# Power.net
KiCad netlist of a schematic drawn in Altium Designer
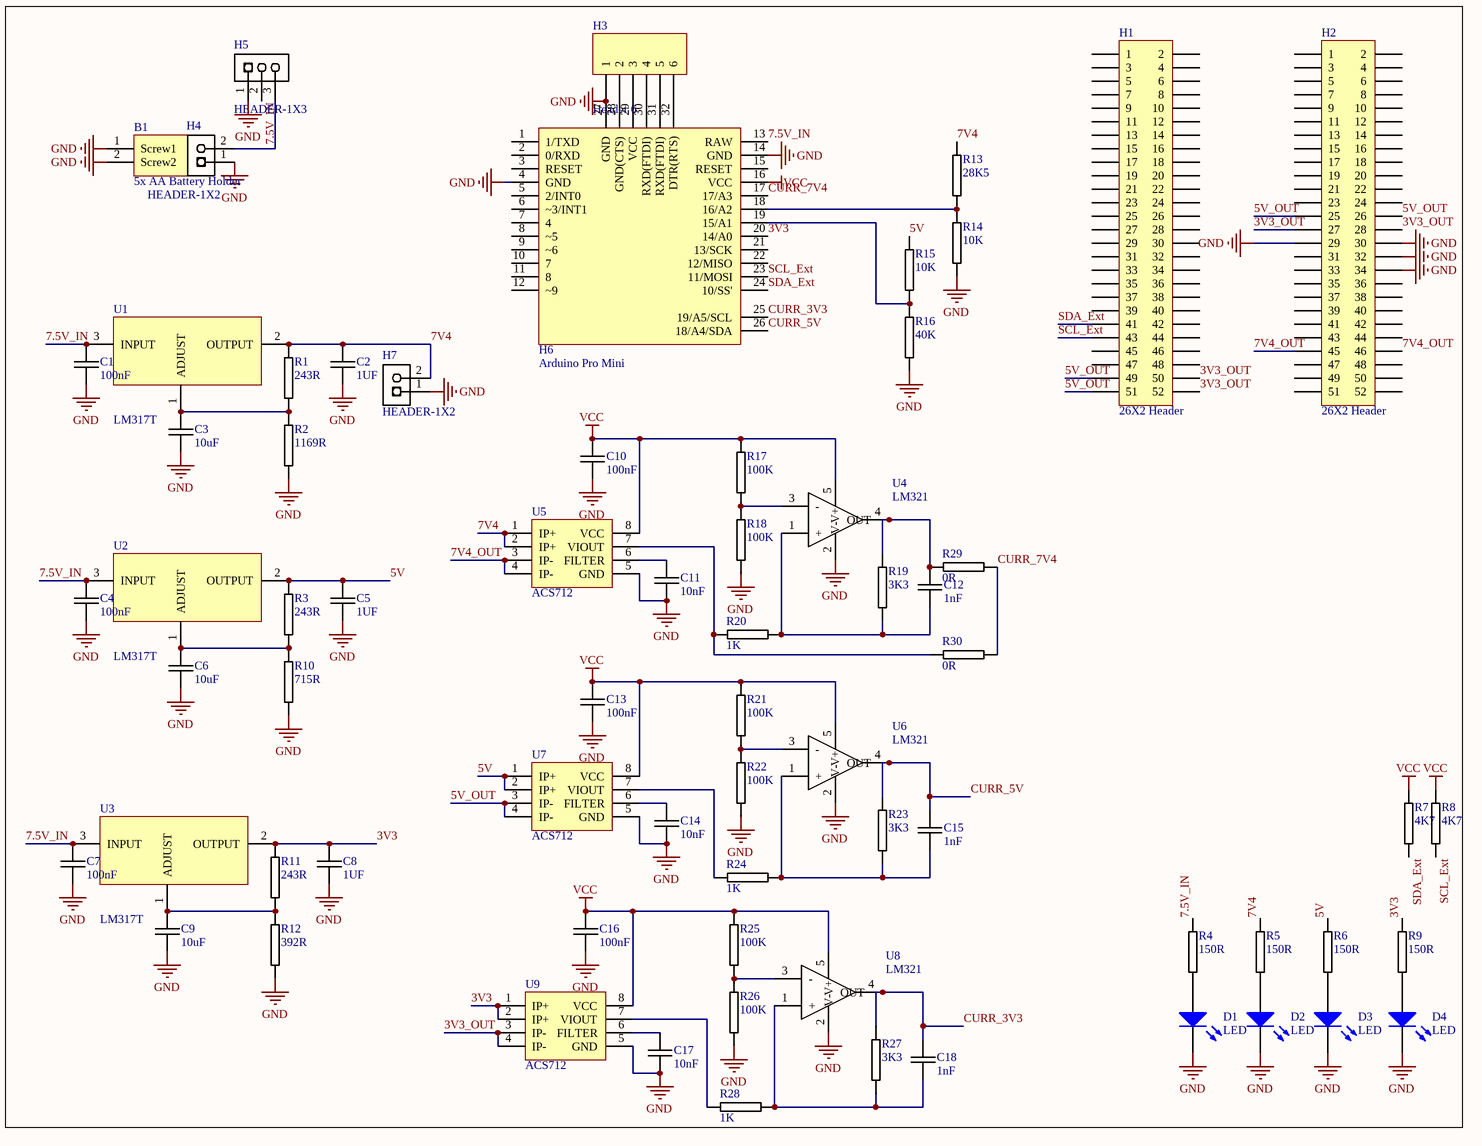
[diagram p0: Power.SchDoc]

(export (version "E")
  (design (tool "Eeschema 10.0.6"))
  (components
    (comp (ref "B1")
      (value "5x AA Battery Holder")
      (footprint "5x AA Battery Holder")
      (libsource (lib "Components") (part "5x AA Battery Holder"))
    )
    (comp (ref "C1")
      (value "100nF")
      (footprint "0805C-TBD")
      (description "CAPACITOR 0805 CERAMIC")
      (libsource (lib "vh_altium_library") (part "0805C-100nF-25V-X7R-MUR"))
    )
    (comp (ref "C2")
      (value "1UF")
      (footprint "0805C-GENERIC")
      (description "CAPACITOR 0805 CERAMIC")
      (fields
        (field (name "MANUFACTURER PART NUMBER") "ECJ-1VB0J225K")
        (field (name "MANUFACTURER") "Panasonic - ECG")
      )
      (libsource (lib "vh_altium_library") (part "0805C-2U2-6V3-X5R-PAN"))
    )
    (comp (ref "C3")
      (value "10uF")
      (footprint "0805C-GENERIC")
      (description "CAPACITOR 0805 CERAMIC")
      (libsource (lib "vh_altium_library") (part "0805C-10UF-25V-X5R-SAM"))
    )
    (comp (ref "C4")
      (value "100nF")
      (footprint "0805C-TBD")
      (description "CAPACITOR 0805 CERAMIC")
      (libsource (lib "vh_altium_library") (part "0805C-100nF-25V-X7R-MUR"))
    )
    (comp (ref "C5")
      (value "1UF")
      (footprint "0805C-GENERIC")
      (description "CAPACITOR 0805 CERAMIC")
      (fields
        (field (name "MANUFACTURER PART NUMBER") "ECJ-1VB0J225K")
        (field (name "MANUFACTURER") "Panasonic - ECG")
      )
      (libsource (lib "vh_altium_library") (part "0805C-2U2-6V3-X5R-PAN"))
    )
    (comp (ref "C6")
      (value "10uF")
      (footprint "0805C-GENERIC")
      (description "CAPACITOR 0805 CERAMIC")
      (libsource (lib "vh_altium_library") (part "0805C-10UF-25V-X5R-SAM"))
    )
    (comp (ref "C7")
      (value "100nF")
      (footprint "0805C-TBD")
      (description "CAPACITOR 0805 CERAMIC")
      (libsource (lib "vh_altium_library") (part "0805C-100nF-25V-X7R-MUR"))
    )
    (comp (ref "C8")
      (value "1UF")
      (footprint "0805C-GENERIC")
      (description "CAPACITOR 0805 CERAMIC")
      (fields
        (field (name "MANUFACTURER PART NUMBER") "ECJ-1VB0J225K")
        (field (name "MANUFACTURER") "Panasonic - ECG")
      )
      (libsource (lib "vh_altium_library") (part "0805C-2U2-6V3-X5R-PAN"))
    )
    (comp (ref "C9")
      (value "10uF")
      (footprint "0805C-GENERIC")
      (description "CAPACITOR 0805 CERAMIC")
      (libsource (lib "vh_altium_library") (part "0805C-10UF-25V-X5R-SAM"))
    )
    (comp (ref "C10")
      (value "100nF")
      (footprint "0805C-TBD")
      (description "CAPACITOR 0805 CERAMIC")
      (libsource (lib "vh_altium_library") (part "0805C-100nF-25V-X7R-MUR"))
    )
    (comp (ref "C11")
      (value "10nF")
      (footprint "0805C-TBD")
      (description "CAPACITOR 0805 CERAMIC")
      (libsource (lib "vh_altium_library") (part "0805C-100nF-25V-X7R-MUR"))
    )
    (comp (ref "C12")
      (value "1nF")
      (footprint "0805C-TBD")
      (description "CAPACITOR 0805 CERAMIC")
      (libsource (lib "vh_altium_library") (part "0805C-100nF-25V-X7R-MUR"))
    )
    (comp (ref "C13")
      (value "100nF")
      (footprint "0805C-TBD")
      (description "CAPACITOR 0805 CERAMIC")
      (libsource (lib "vh_altium_library") (part "0805C-100nF-25V-X7R-MUR"))
    )
    (comp (ref "C14")
      (value "10nF")
      (footprint "0805C-TBD")
      (description "CAPACITOR 0805 CERAMIC")
      (libsource (lib "vh_altium_library") (part "0805C-100nF-25V-X7R-MUR"))
    )
    (comp (ref "C15")
      (value "1nF")
      (footprint "0805C-TBD")
      (description "CAPACITOR 0805 CERAMIC")
      (libsource (lib "vh_altium_library") (part "0805C-100nF-25V-X7R-MUR"))
    )
    (comp (ref "C16")
      (value "100nF")
      (footprint "0805C-TBD")
      (description "CAPACITOR 0805 CERAMIC")
      (libsource (lib "vh_altium_library") (part "0805C-100nF-25V-X7R-MUR"))
    )
    (comp (ref "C17")
      (value "10nF")
      (footprint "0805C-TBD")
      (description "CAPACITOR 0805 CERAMIC")
      (libsource (lib "vh_altium_library") (part "0805C-100nF-25V-X7R-MUR"))
    )
    (comp (ref "C18")
      (value "1nF")
      (footprint "0805C-TBD")
      (description "CAPACITOR 0805 CERAMIC")
      (libsource (lib "vh_altium_library") (part "0805C-100nF-25V-X7R-MUR"))
    )
    (comp (ref "D1")
      (value "LED")
      (footprint "LED")
      (description "Small LED")
      (libsource (lib "Components") (part "LED"))
    )
    (comp (ref "D2")
      (value "LED")
      (footprint "LED")
      (description "Small LED")
      (libsource (lib "Components") (part "LED"))
    )
    (comp (ref "D3")
      (value "LED")
      (footprint "LED")
      (description "Small LED")
      (libsource (lib "Components") (part "LED"))
    )
    (comp (ref "D4")
      (value "LED")
      (footprint "LED")
      (description "Small LED")
      (libsource (lib "Components") (part "LED"))
    )
    (comp (ref "H1")
      (value "26X2 Header")
      (footprint "26X2 Header")
      (libsource (lib "CustomParts") (part "26X2 Header"))
    )
    (comp (ref "H2")
      (value "26X2 Header")
      (footprint "26X2 Header")
      (libsource (lib "CustomParts") (part "26X2 Header"))
    )
    (comp (ref "H3")
      (value "Header 6")
      (footprint "HDR1X6")
      (description "Header, 6-Pin")
      (fields (field (name "PUBLISHER") "Altium Limited"))
      (libsource (lib "Miscellaneous Connectors") (part "Header 6"))
    )
    (comp (ref "H4")
      (value "HEADER-1X2")
      (footprint "HEADER-1X2")
      (libsource (lib "vh_altium_library") (part "HEADER-1X2"))
    )
    (comp (ref "H5")
      (value "HEADER-1X3")
      (footprint "HEADER-1X3")
      (libsource (lib "vh_altium_library") (part "HEADER-1X3"))
    )
    (comp (ref "H6")
      (value "Arduino Pro Mini")
      (footprint "Arduino Pro Mini")
      (libsource (lib "Components") (part "Arduino Pro Mini"))
    )
    (comp (ref "H7")
      (value "HEADER-1X2")
      (footprint "HEADER-1X2")
      (libsource (lib "vh_altium_library") (part "HEADER-1X2"))
    )
    (comp (ref "R1")
      (value "243R")
      (footprint "0805R-GENERIC")
      (description "RESISTOR 0805 1/3 WATT")
      (libsource (lib "vh_altium_library") (part "0805R-1R"))
    )
    (comp (ref "R2")
      (value "1169R")
      (footprint "0805R-GENERIC")
      (description "RESISTOR 0805 1/3 WATT")
      (libsource (lib "vh_altium_library") (part "0805R-1R"))
    )
    (comp (ref "R3")
      (value "243R")
      (footprint "0805R-GENERIC")
      (description "RESISTOR 0805 1/3 WATT")
      (libsource (lib "vh_altium_library") (part "0805R-1R"))
    )
    (comp (ref "R4")
      (value "150R")
      (footprint "0805R-150")
      (description "RESISTOR 0805 1/4 WATT THIN FILM")
      (libsource (lib "vh_altium_library") (part "0805R-150"))
    )
    (comp (ref "R5")
      (value "150R")
      (footprint "0805R-150")
      (description "RESISTOR 0805 1/4 WATT THIN FILM")
      (libsource (lib "vh_altium_library") (part "0805R-150"))
    )
    (comp (ref "R6")
      (value "150R")
      (footprint "0805R-150")
      (description "RESISTOR 0805 1/4 WATT THIN FILM")
      (libsource (lib "vh_altium_library") (part "0805R-150"))
    )
    (comp (ref "R7")
      (value "4K7")
      (footprint "0805R-4K7")
      (description "RESISTOR 0805 1/4 WATT THIN FILM")
      (libsource (lib "vh_altium_library") (part "0805R-4K7"))
    )
    (comp (ref "R8")
      (value "4K7")
      (footprint "0805R-4K7")
      (description "RESISTOR 0805 1/4 WATT THIN FILM")
      (libsource (lib "vh_altium_library") (part "0805R-4K7"))
    )
    (comp (ref "R9")
      (value "150R")
      (footprint "0805R-150")
      (description "RESISTOR 0805 1/4 WATT THIN FILM")
      (libsource (lib "vh_altium_library") (part "0805R-150"))
    )
    (comp (ref "R10")
      (value "715R")
      (footprint "0805R-GENERIC")
      (description "RESISTOR 0805 1/3 WATT")
      (libsource (lib "vh_altium_library") (part "0805R-1R"))
    )
    (comp (ref "R11")
      (value "243R")
      (footprint "0805R-GENERIC")
      (description "RESISTOR 0805 1/3 WATT")
      (libsource (lib "vh_altium_library") (part "0805R-1R"))
    )
    (comp (ref "R12")
      (value "392R")
      (footprint "0805R-GENERIC")
      (description "RESISTOR 0805 1/3 WATT")
      (libsource (lib "vh_altium_library") (part "0805R-1R"))
    )
    (comp (ref "R13")
      (value "28K5")
      (footprint "0805R-10K")
      (description "RESISTOR 0805 1/4 WATT THIN FILM")
      (libsource (lib "vh_altium_library") (part "0805R-10K"))
    )
    (comp (ref "R14")
      (value "10K")
      (footprint "0805R-10K")
      (description "RESISTOR 0805 1/4 WATT THIN FILM")
      (libsource (lib "vh_altium_library") (part "0805R-10K"))
    )
    (comp (ref "R15")
      (value "10K")
      (footprint "0805R-10K")
      (description "RESISTOR 0805 1/4 WATT THIN FILM")
      (libsource (lib "vh_altium_library") (part "0805R-10K"))
    )
    (comp (ref "R16")
      (value "40K")
      (footprint "0805R-10K")
      (description "RESISTOR 0805 1/4 WATT THIN FILM")
      (libsource (lib "vh_altium_library") (part "0805R-10K"))
    )
    (comp (ref "R17")
      (value "100K")
      (footprint "0805R-100K")
      (description "RESISTOR 0805 1/4 WATT THIN FILM")
      (libsource (lib "vh_altium_library") (part "0805R-100K"))
    )
    (comp (ref "R18")
      (value "100K")
      (footprint "0805R-100K")
      (description "RESISTOR 0805 1/4 WATT THIN FILM")
      (libsource (lib "vh_altium_library") (part "0805R-100K"))
    )
    (comp (ref "R19")
      (value "3K3")
      (footprint "0805R-3K3")
      (description "RESISTOR 0805 1/4 WATT THIN FILM")
      (libsource (lib "vh_altium_library") (part "0805R-3K3"))
    )
    (comp (ref "R20")
      (value "1K")
      (footprint "0805R-1K")
      (description "RESISTOR 0805 1/4 WATT THIN FILM")
      (libsource (lib "vh_altium_library") (part "0805R-1K"))
    )
    (comp (ref "R21")
      (value "100K")
      (footprint "0805R-100K")
      (description "RESISTOR 0805 1/4 WATT THIN FILM")
      (libsource (lib "vh_altium_library") (part "0805R-100K"))
    )
    (comp (ref "R22")
      (value "100K")
      (footprint "0805R-100K")
      (description "RESISTOR 0805 1/4 WATT THIN FILM")
      (libsource (lib "vh_altium_library") (part "0805R-100K"))
    )
    (comp (ref "R23")
      (value "3K3")
      (footprint "0805R-3K3")
      (description "RESISTOR 0805 1/4 WATT THIN FILM")
      (libsource (lib "vh_altium_library") (part "0805R-3K3"))
    )
    (comp (ref "R24")
      (value "1K")
      (footprint "0805R-1K")
      (description "RESISTOR 0805 1/4 WATT THIN FILM")
      (libsource (lib "vh_altium_library") (part "0805R-1K"))
    )
    (comp (ref "R25")
      (value "100K")
      (footprint "0805R-100K")
      (description "RESISTOR 0805 1/4 WATT THIN FILM")
      (libsource (lib "vh_altium_library") (part "0805R-100K"))
    )
    (comp (ref "R26")
      (value "100K")
      (footprint "0805R-100K")
      (description "RESISTOR 0805 1/4 WATT THIN FILM")
      (libsource (lib "vh_altium_library") (part "0805R-100K"))
    )
    (comp (ref "R27")
      (value "3K3")
      (footprint "0805R-3K3")
      (description "RESISTOR 0805 1/4 WATT THIN FILM")
      (libsource (lib "vh_altium_library") (part "0805R-3K3"))
    )
    (comp (ref "R28")
      (value "1K")
      (footprint "0805R-1K")
      (description "RESISTOR 0805 1/4 WATT THIN FILM")
      (libsource (lib "vh_altium_library") (part "0805R-1K"))
    )
    (comp (ref "R29")
      (value "0R")
      (footprint "0805R-GENERIC")
      (description "RESISTOR 0805 1 WATT")
      (libsource (lib "vh_altium_library") (part "0805R-0R"))
    )
    (comp (ref "R30")
      (value "0R")
      (footprint "0805R-GENERIC")
      (description "RESISTOR 0805 1 WATT")
      (libsource (lib "vh_altium_library") (part "0805R-0R"))
    )
    (comp (ref "U1")
      (value "LM317T")
      (footprint "LM317T")
      (description "Adjustable Voltage Regulator")
      (libsource (lib "Components") (part "LM317T"))
    )
    (comp (ref "U2")
      (value "LM317T")
      (footprint "LM317T")
      (description "Adjustable Voltage Regulator")
      (libsource (lib "Components") (part "LM317T"))
    )
    (comp (ref "U3")
      (value "LM317T")
      (footprint "LM317T")
      (description "Adjustable Voltage Regulator")
      (libsource (lib "Components") (part "LM317T"))
    )
    (comp (ref "U4")
      (value "LM321")
      (footprint "LM321")
      (description "Op-amp")
      (libsource (lib "Components") (part "LM321"))
    )
    (comp (ref "U5")
      (value "ACS712")
      (footprint "ACS712")
      (description "Current Sensor")
      (libsource (lib "Components") (part "ACS712"))
    )
    (comp (ref "U6")
      (value "LM321")
      (footprint "LM321")
      (description "Op-amp")
      (libsource (lib "Components") (part "LM321"))
    )
    (comp (ref "U7")
      (value "ACS712")
      (footprint "ACS712")
      (description "Current Sensor")
      (libsource (lib "Components") (part "ACS712"))
    )
    (comp (ref "U8")
      (value "LM321")
      (footprint "LM321")
      (description "Op-amp")
      (libsource (lib "Components") (part "LM321"))
    )
    (comp (ref "U9")
      (value "ACS712")
      (footprint "ACS712")
      (description "Current Sensor")
      (libsource (lib "Components") (part "ACS712"))
    )
  )
  (nets
    (net (code "1") (name "/3V3") (class "Default")
      (node (ref "C8") (pin "1") (pintype "passive"))
      (node (ref "H6") (pin "20") (pinfunction "14/A0_20") (pintype "passive"))
      (node (ref "R11") (pin "2") (pintype "passive"))
      (node (ref "R9") (pin "1") (pintype "passive"))
      (node (ref "U3") (pin "2") (pinfunction "OUTPUT_2") (pintype "passive"))
      (node (ref "U9") (pin "1") (pinfunction "IP+_1") (pintype "passive"))
      (node (ref "U9") (pin "2") (pinfunction "IP+_2") (pintype "passive"))
    )
    (net (code "2") (name "/3V3_OUT") (class "Default")
      (node (ref "H1") (pin "50") (pinfunction "50_50") (pintype "passive"))
      (node (ref "H1") (pin "52") (pinfunction "52_52") (pintype "passive"))
      (node (ref "H2") (pin "27") (pinfunction "27_27") (pintype "passive"))
      (node (ref "H2") (pin "28") (pinfunction "28_28") (pintype "passive"))
      (node (ref "U9") (pin "3") (pinfunction "IP-_3") (pintype "passive"))
      (node (ref "U9") (pin "4") (pinfunction "IP-_4") (pintype "passive"))
    )
    (net (code "3") (name "/5V") (class "Default")
      (node (ref "C5") (pin "1") (pintype "passive"))
      (node (ref "R15") (pin "1") (pintype "passive"))
      (node (ref "R3") (pin "2") (pintype "passive"))
      (node (ref "R6") (pin "1") (pintype "passive"))
      (node (ref "U2") (pin "2") (pinfunction "OUTPUT_2") (pintype "passive"))
      (node (ref "U7") (pin "1") (pinfunction "IP+_1") (pintype "passive"))
      (node (ref "U7") (pin "2") (pinfunction "IP+_2") (pintype "passive"))
    )
    (net (code "4") (name "/5V_OUT") (class "Default")
      (node (ref "H1") (pin "49") (pinfunction "49_49") (pintype "passive"))
      (node (ref "H1") (pin "51") (pinfunction "51_51") (pintype "passive"))
      (node (ref "H2") (pin "25") (pinfunction "25_25") (pintype "passive"))
      (node (ref "H2") (pin "26") (pinfunction "26_26") (pintype "passive"))
      (node (ref "U7") (pin "3") (pinfunction "IP-_3") (pintype "passive"))
      (node (ref "U7") (pin "4") (pinfunction "IP-_4") (pintype "passive"))
    )
    (net (code "5") (name "/7.5V_IN") (class "Default")
      (node (ref "C1") (pin "1") (pintype "passive"))
      (node (ref "C4") (pin "1") (pintype "passive"))
      (node (ref "C7") (pin "1") (pintype "passive"))
      (node (ref "H5") (pin "2") (pintype "passive"))
      (node (ref "H6") (pin "13") (pinfunction "RAW_13") (pintype "passive"))
      (node (ref "R4") (pin "1") (pintype "passive"))
      (node (ref "U1") (pin "3") (pinfunction "INPUT_3") (pintype "passive"))
      (node (ref "U2") (pin "3") (pinfunction "INPUT_3") (pintype "passive"))
      (node (ref "U3") (pin "3") (pinfunction "INPUT_3") (pintype "passive"))
    )
    (net (code "6") (name "/7V4") (class "Default")
      (node (ref "C2") (pin "1") (pintype "passive"))
      (node (ref "H7") (pin "2") (pintype "passive"))
      (node (ref "R1") (pin "2") (pintype "passive"))
      (node (ref "R13") (pin "1") (pintype "passive"))
      (node (ref "R5") (pin "1") (pintype "passive"))
      (node (ref "U1") (pin "2") (pinfunction "OUTPUT_2") (pintype "passive"))
      (node (ref "U5") (pin "1") (pinfunction "IP+_1") (pintype "passive"))
      (node (ref "U5") (pin "2") (pinfunction "IP+_2") (pintype "passive"))
    )
    (net (code "7") (name "/7V4_OUT") (class "Default")
      (node (ref "H2") (pin "45") (pinfunction "45_45") (pintype "passive"))
      (node (ref "H2") (pin "46") (pinfunction "46_46") (pintype "passive"))
      (node (ref "U5") (pin "3") (pinfunction "IP-_3") (pintype "passive"))
      (node (ref "U5") (pin "4") (pinfunction "IP-_4") (pintype "passive"))
    )
    (net (code "8") (name "/CURR_3V3") (class "Default")
      (node (ref "C18") (pin "1") (pintype "passive"))
      (node (ref "H6") (pin "25") (pinfunction "19/A5/SCL_25") (pintype "passive"))
      (node (ref "R27") (pin "1") (pintype "passive"))
      (node (ref "U8") (pin "4") (pinfunction "OUT_4") (pintype "passive"))
    )
    (net (code "9") (name "/CURR_5V") (class "Default")
      (node (ref "C15") (pin "1") (pintype "passive"))
      (node (ref "H6") (pin "26") (pinfunction "18/A4/SDA_26") (pintype "passive"))
      (node (ref "R23") (pin "1") (pintype "passive"))
      (node (ref "U6") (pin "4") (pinfunction "OUT_4") (pintype "passive"))
    )
    (net (code "10") (name "/CURR_7V4") (class "Default")
      (node (ref "H6") (pin "17") (pinfunction "17/A3_17") (pintype "passive"))
      (node (ref "R29") (pin "2") (pintype "passive"))
      (node (ref "R30") (pin "2") (pintype "passive"))
    )
    (net (code "11") (name "/SCL_Ext") (class "Default")
      (node (ref "H1") (pin "43") (pinfunction "43_43") (pintype "passive"))
      (node (ref "H6") (pin "23") (pinfunction "11/MOSI_23") (pintype "passive"))
      (node (ref "R8") (pin "2") (pintype "passive"))
    )
    (net (code "12") (name "/SDA_Ext") (class "Default")
      (node (ref "H1") (pin "41") (pinfunction "41_41") (pintype "passive"))
      (node (ref "H6") (pin "24") (pinfunction "10/SS'_24") (pintype "passive"))
      (node (ref "R7") (pin "2") (pintype "passive"))
    )
    (net (code "13") (name "GND") (class "Default")
      (node (ref "B1") (pin "1") (pinfunction "Screw1_1") (pintype "passive"))
      (node (ref "B1") (pin "2") (pinfunction "Screw2_2") (pintype "passive"))
      (node (ref "C1") (pin "2") (pintype "passive"))
      (node (ref "C10") (pin "2") (pintype "passive"))
      (node (ref "C11") (pin "2") (pintype "passive"))
      (node (ref "C13") (pin "2") (pintype "passive"))
      (node (ref "C14") (pin "2") (pintype "passive"))
      (node (ref "C16") (pin "2") (pintype "passive"))
      (node (ref "C17") (pin "2") (pintype "passive"))
      (node (ref "C2") (pin "2") (pintype "passive"))
      (node (ref "C3") (pin "2") (pintype "passive"))
      (node (ref "C4") (pin "2") (pintype "passive"))
      (node (ref "C5") (pin "2") (pintype "passive"))
      (node (ref "C6") (pin "2") (pintype "passive"))
      (node (ref "C7") (pin "2") (pintype "passive"))
      (node (ref "C8") (pin "2") (pintype "passive"))
      (node (ref "C9") (pin "2") (pintype "passive"))
      (node (ref "D1") (pin "2") (pinfunction "K_2") (pintype "passive"))
      (node (ref "D2") (pin "2") (pinfunction "K_2") (pintype "passive"))
      (node (ref "D3") (pin "2") (pinfunction "K_2") (pintype "passive"))
      (node (ref "D4") (pin "2") (pinfunction "K_2") (pintype "passive"))
      (node (ref "H2") (pin "29") (pinfunction "29_29") (pintype "passive"))
      (node (ref "H2") (pin "30") (pinfunction "30_30") (pintype "passive"))
      (node (ref "H2") (pin "32") (pinfunction "32_32") (pintype "passive"))
      (node (ref "H2") (pin "34") (pinfunction "34_34") (pintype "passive"))
      (node (ref "H3") (pin "1") (pinfunction "1_1") (pintype "passive"))
      (node (ref "H4") (pin "1") (pintype "passive"))
      (node (ref "H5") (pin "1") (pintype "passive"))
      (node (ref "H6") (pin "14") (pinfunction "GND_14") (pintype "passive"))
      (node (ref "H6") (pin "27") (pinfunction "GND_27") (pintype "passive"))
      (node (ref "H6") (pin "4") (pinfunction "GND_4") (pintype "passive"))
      (node (ref "H7") (pin "1") (pintype "passive"))
      (node (ref "R10") (pin "2") (pintype "passive"))
      (node (ref "R12") (pin "2") (pintype "passive"))
      (node (ref "R14") (pin "2") (pintype "passive"))
      (node (ref "R16") (pin "2") (pintype "passive"))
      (node (ref "R18") (pin "2") (pintype "passive"))
      (node (ref "R2") (pin "2") (pintype "passive"))
      (node (ref "R22") (pin "2") (pintype "passive"))
      (node (ref "R26") (pin "2") (pintype "passive"))
      (node (ref "U4") (pin "2") (pinfunction "V-_2") (pintype "passive"))
      (node (ref "U5") (pin "5") (pinfunction "GND_5") (pintype "passive"))
      (node (ref "U6") (pin "2") (pinfunction "V-_2") (pintype "passive"))
      (node (ref "U7") (pin "5") (pinfunction "GND_5") (pintype "passive"))
      (node (ref "U8") (pin "2") (pinfunction "V-_2") (pintype "passive"))
      (node (ref "U9") (pin "5") (pinfunction "GND_5") (pintype "passive"))
    )
    (net (code "14") (name "Net-(D1-A)") (class "Default")
      (node (ref "D1") (pin "1") (pinfunction "A_1") (pintype "passive"))
      (node (ref "R4") (pin "2") (pintype "passive"))
    )
    (net (code "15") (name "Net-(D2-A)") (class "Default")
      (node (ref "D2") (pin "1") (pinfunction "A_1") (pintype "passive"))
      (node (ref "R5") (pin "2") (pintype "passive"))
    )
    (net (code "16") (name "Net-(D3-A)") (class "Default")
      (node (ref "D3") (pin "1") (pinfunction "A_1") (pintype "passive"))
      (node (ref "R6") (pin "2") (pintype "passive"))
    )
    (net (code "17") (name "Net-(D4-A)") (class "Default")
      (node (ref "D4") (pin "1") (pinfunction "A_1") (pintype "passive"))
      (node (ref "R9") (pin "2") (pintype "passive"))
    )
    (net (code "18") (name "Net-(H3-Pad3)") (class "Default")
      (node (ref "H3") (pin "3") (pinfunction "3_3") (pintype "passive"))
      (node (ref "H6") (pin "29") (pinfunction "VCC_29") (pintype "passive"))
    )
    (net (code "19") (name "Net-(H3-Pad4)") (class "Default")
      (node (ref "H3") (pin "4") (pinfunction "4_4") (pintype "passive"))
      (node (ref "H6") (pin "30") (pinfunction "RXD(FTDI)_30") (pintype "passive"))
    )
    (net (code "20") (name "Net-(H3-Pad5)") (class "Default")
      (node (ref "H3") (pin "5") (pinfunction "5_5") (pintype "passive"))
      (node (ref "H6") (pin "31") (pinfunction "RXD(FTDI)_31") (pintype "passive"))
    )
    (net (code "21") (name "Net-(H4-Pad2)") (class "Default")
      (node (ref "H4") (pin "2") (pintype "passive"))
      (node (ref "H5") (pin "3") (pintype "passive"))
    )
    (net (code "22") (name "Net-(H6-15{slash}A1)") (class "Default")
      (node (ref "H6") (pin "19") (pinfunction "15/A1_19") (pintype "passive"))
      (node (ref "R15") (pin "2") (pintype "passive"))
      (node (ref "R16") (pin "1") (pintype "passive"))
    )
    (net (code "23") (name "Net-(H6-16{slash}A2)") (class "Default")
      (node (ref "H6") (pin "18") (pinfunction "16/A2_18") (pintype "passive"))
      (node (ref "R13") (pin "2") (pintype "passive"))
      (node (ref "R14") (pin "1") (pintype "passive"))
    )
    (net (code "24") (name "Net-(H6-DTR(RTS))") (class "Default")
      (node (ref "H3") (pin "6") (pinfunction "6_6") (pintype "passive"))
      (node (ref "H6") (pin "32") (pinfunction "DTR(RTS)_32") (pintype "passive"))
    )
    (net (code "25") (name "Net-(H6-GND(CTS))") (class "Default")
      (node (ref "H3") (pin "2") (pinfunction "2_2") (pintype "passive"))
      (node (ref "H6") (pin "28") (pinfunction "GND(CTS)_28") (pintype "passive"))
    )
    (net (code "26") (name "Net-(U1-ADJUST)") (class "Default")
      (node (ref "C3") (pin "1") (pintype "passive"))
      (node (ref "R1") (pin "1") (pintype "passive"))
      (node (ref "R2") (pin "1") (pintype "passive"))
      (node (ref "U1") (pin "1") (pinfunction "ADJUST_1") (pintype "passive"))
    )
    (net (code "27") (name "Net-(U2-ADJUST)") (class "Default")
      (node (ref "C6") (pin "1") (pintype "passive"))
      (node (ref "R10") (pin "1") (pintype "passive"))
      (node (ref "R3") (pin "1") (pintype "passive"))
      (node (ref "U2") (pin "1") (pinfunction "ADJUST_1") (pintype "passive"))
    )
    (net (code "28") (name "Net-(U3-ADJUST)") (class "Default")
      (node (ref "C9") (pin "1") (pintype "passive"))
      (node (ref "R11") (pin "1") (pintype "passive"))
      (node (ref "R12") (pin "1") (pintype "passive"))
      (node (ref "U3") (pin "1") (pinfunction "ADJUST_1") (pintype "passive"))
    )
    (net (code "29") (name "Net-(U4-+)") (class "Default")
      (node (ref "C12") (pin "2") (pintype "passive"))
      (node (ref "R19") (pin "2") (pintype "passive"))
      (node (ref "R20") (pin "2") (pintype "passive"))
      (node (ref "U4") (pin "1") (pinfunction "+_1") (pintype "passive"))
    )
    (net (code "30") (name "Net-(U4--)") (class "Default")
      (node (ref "R17") (pin "2") (pintype "passive"))
      (node (ref "R18") (pin "1") (pintype "passive"))
      (node (ref "U4") (pin "3") (pinfunction "-_3") (pintype "passive"))
    )
    (net (code "31") (name "Net-(U4-OUT)") (class "Default")
      (node (ref "C12") (pin "1") (pintype "passive"))
      (node (ref "R19") (pin "1") (pintype "passive"))
      (node (ref "R29") (pin "1") (pintype "passive"))
      (node (ref "U4") (pin "4") (pinfunction "OUT_4") (pintype "passive"))
    )
    (net (code "32") (name "Net-(U5-FILTER)") (class "Default")
      (node (ref "C11") (pin "1") (pintype "passive"))
      (node (ref "U5") (pin "6") (pinfunction "FILTER_6") (pintype "passive"))
    )
    (net (code "33") (name "Net-(U5-VIOUT)") (class "Default")
      (node (ref "R20") (pin "1") (pintype "passive"))
      (node (ref "R30") (pin "1") (pintype "passive"))
      (node (ref "U5") (pin "7") (pinfunction "VIOUT_7") (pintype "passive"))
    )
    (net (code "34") (name "Net-(U6-+)") (class "Default")
      (node (ref "C15") (pin "2") (pintype "passive"))
      (node (ref "R23") (pin "2") (pintype "passive"))
      (node (ref "R24") (pin "2") (pintype "passive"))
      (node (ref "U6") (pin "1") (pinfunction "+_1") (pintype "passive"))
    )
    (net (code "35") (name "Net-(U6--)") (class "Default")
      (node (ref "R21") (pin "2") (pintype "passive"))
      (node (ref "R22") (pin "1") (pintype "passive"))
      (node (ref "U6") (pin "3") (pinfunction "-_3") (pintype "passive"))
    )
    (net (code "36") (name "Net-(U7-FILTER)") (class "Default")
      (node (ref "C14") (pin "1") (pintype "passive"))
      (node (ref "U7") (pin "6") (pinfunction "FILTER_6") (pintype "passive"))
    )
    (net (code "37") (name "Net-(U7-VIOUT)") (class "Default")
      (node (ref "R24") (pin "1") (pintype "passive"))
      (node (ref "U7") (pin "7") (pinfunction "VIOUT_7") (pintype "passive"))
    )
    (net (code "38") (name "Net-(U8-+)") (class "Default")
      (node (ref "C18") (pin "2") (pintype "passive"))
      (node (ref "R27") (pin "2") (pintype "passive"))
      (node (ref "R28") (pin "2") (pintype "passive"))
      (node (ref "U8") (pin "1") (pinfunction "+_1") (pintype "passive"))
    )
    (net (code "39") (name "Net-(U8--)") (class "Default")
      (node (ref "R25") (pin "2") (pintype "passive"))
      (node (ref "R26") (pin "1") (pintype "passive"))
      (node (ref "U8") (pin "3") (pinfunction "-_3") (pintype "passive"))
    )
    (net (code "40") (name "Net-(U9-FILTER)") (class "Default")
      (node (ref "C17") (pin "1") (pintype "passive"))
      (node (ref "U9") (pin "6") (pinfunction "FILTER_6") (pintype "passive"))
    )
    (net (code "41") (name "Net-(U9-VIOUT)") (class "Default")
      (node (ref "R28") (pin "1") (pintype "passive"))
      (node (ref "U9") (pin "7") (pinfunction "VIOUT_7") (pintype "passive"))
    )
    (net (code "42") (name "VCC") (class "Default")
      (node (ref "C10") (pin "1") (pintype "passive"))
      (node (ref "C13") (pin "1") (pintype "passive"))
      (node (ref "C16") (pin "1") (pintype "passive"))
      (node (ref "H6") (pin "16") (pinfunction "VCC_16") (pintype "passive"))
      (node (ref "R17") (pin "1") (pintype "passive"))
      (node (ref "R21") (pin "1") (pintype "passive"))
      (node (ref "R25") (pin "1") (pintype "passive"))
      (node (ref "R7") (pin "1") (pintype "passive"))
      (node (ref "R8") (pin "1") (pintype "passive"))
      (node (ref "U4") (pin "5") (pinfunction "V+_5") (pintype "passive"))
      (node (ref "U5") (pin "8") (pinfunction "VCC_8") (pintype "passive"))
      (node (ref "U6") (pin "5") (pinfunction "V+_5") (pintype "passive"))
      (node (ref "U7") (pin "8") (pinfunction "VCC_8") (pintype "passive"))
      (node (ref "U8") (pin "5") (pinfunction "V+_5") (pintype "passive"))
      (node (ref "U9") (pin "8") (pinfunction "VCC_8") (pintype "passive"))
    )
    (net (code "43") (name "unconnected-(H1-Pad1)") (class "Default")
      (node (ref "H1") (pin "1") (pinfunction "1_1") (pintype "passive"))
    )
    (net (code "44") (name "unconnected-(H1-Pad2)") (class "Default")
      (node (ref "H1") (pin "2") (pinfunction "2_2") (pintype "passive"))
    )
    (net (code "45") (name "unconnected-(H1-Pad3)") (class "Default")
      (node (ref "H1") (pin "3") (pinfunction "3_3") (pintype "passive"))
    )
    (net (code "46") (name "unconnected-(H1-Pad4)") (class "Default")
      (node (ref "H1") (pin "4") (pinfunction "4_4") (pintype "passive"))
    )
    (net (code "47") (name "unconnected-(H1-Pad5)") (class "Default")
      (node (ref "H1") (pin "5") (pinfunction "5_5") (pintype "passive"))
    )
    (net (code "48") (name "unconnected-(H1-Pad6)") (class "Default")
      (node (ref "H1") (pin "6") (pinfunction "6_6") (pintype "passive"))
    )
    (net (code "49") (name "unconnected-(H1-Pad7)") (class "Default")
      (node (ref "H1") (pin "7") (pinfunction "7_7") (pintype "passive"))
    )
    (net (code "50") (name "unconnected-(H1-Pad8)") (class "Default")
      (node (ref "H1") (pin "8") (pinfunction "8_8") (pintype "passive"))
    )
    (net (code "51") (name "unconnected-(H1-Pad9)") (class "Default")
      (node (ref "H1") (pin "9") (pinfunction "9_9") (pintype "passive"))
    )
    (net (code "52") (name "unconnected-(H1-Pad10)") (class "Default")
      (node (ref "H1") (pin "10") (pinfunction "10_10") (pintype "passive"))
    )
    (net (code "53") (name "unconnected-(H1-Pad11)") (class "Default")
      (node (ref "H1") (pin "11") (pinfunction "11_11") (pintype "passive"))
    )
    (net (code "54") (name "unconnected-(H1-Pad12)") (class "Default")
      (node (ref "H1") (pin "12") (pinfunction "12_12") (pintype "passive"))
    )
    (net (code "55") (name "unconnected-(H1-Pad13)") (class "Default")
      (node (ref "H1") (pin "13") (pinfunction "13_13") (pintype "passive"))
    )
    (net (code "56") (name "unconnected-(H1-Pad14)") (class "Default")
      (node (ref "H1") (pin "14") (pinfunction "14_14") (pintype "passive"))
    )
    (net (code "57") (name "unconnected-(H1-Pad15)") (class "Default")
      (node (ref "H1") (pin "15") (pinfunction "15_15") (pintype "passive"))
    )
    (net (code "58") (name "unconnected-(H1-Pad16)") (class "Default")
      (node (ref "H1") (pin "16") (pinfunction "16_16") (pintype "passive"))
    )
    (net (code "59") (name "unconnected-(H1-Pad17)") (class "Default")
      (node (ref "H1") (pin "17") (pinfunction "17_17") (pintype "passive"))
    )
    (net (code "60") (name "unconnected-(H1-Pad18)") (class "Default")
      (node (ref "H1") (pin "18") (pinfunction "18_18") (pintype "passive"))
    )
    (net (code "61") (name "unconnected-(H1-Pad19)") (class "Default")
      (node (ref "H1") (pin "19") (pinfunction "19_19") (pintype "passive"))
    )
    (net (code "62") (name "unconnected-(H1-Pad20)") (class "Default")
      (node (ref "H1") (pin "20") (pinfunction "20_20") (pintype "passive"))
    )
    (net (code "63") (name "unconnected-(H1-Pad21)") (class "Default")
      (node (ref "H1") (pin "21") (pinfunction "21_21") (pintype "passive"))
    )
    (net (code "64") (name "unconnected-(H1-Pad22)") (class "Default")
      (node (ref "H1") (pin "22") (pinfunction "22_22") (pintype "passive"))
    )
    (net (code "65") (name "unconnected-(H1-Pad23)") (class "Default")
      (node (ref "H1") (pin "23") (pinfunction "23_23") (pintype "passive"))
    )
    (net (code "66") (name "unconnected-(H1-Pad24)") (class "Default")
      (node (ref "H1") (pin "24") (pinfunction "24_24") (pintype "passive"))
    )
    (net (code "67") (name "unconnected-(H1-Pad25)") (class "Default")
      (node (ref "H1") (pin "25") (pinfunction "25_25") (pintype "passive"))
    )
    (net (code "68") (name "unconnected-(H1-Pad26)") (class "Default")
      (node (ref "H1") (pin "26") (pinfunction "26_26") (pintype "passive"))
    )
    (net (code "69") (name "unconnected-(H1-Pad27)") (class "Default")
      (node (ref "H1") (pin "27") (pinfunction "27_27") (pintype "passive"))
    )
    (net (code "70") (name "unconnected-(H1-Pad28)") (class "Default")
      (node (ref "H1") (pin "28") (pinfunction "28_28") (pintype "passive"))
    )
    (net (code "71") (name "unconnected-(H1-Pad29)") (class "Default")
      (node (ref "H1") (pin "29") (pinfunction "29_29") (pintype "passive"))
    )
    (net (code "72") (name "unconnected-(H1-Pad30)") (class "Default")
      (node (ref "H1") (pin "30") (pinfunction "30_30") (pintype "passive"))
    )
    (net (code "73") (name "unconnected-(H1-Pad31)") (class "Default")
      (node (ref "H1") (pin "31") (pinfunction "31_31") (pintype "passive"))
    )
    (net (code "74") (name "unconnected-(H1-Pad32)") (class "Default")
      (node (ref "H1") (pin "32") (pinfunction "32_32") (pintype "passive"))
    )
    (net (code "75") (name "unconnected-(H1-Pad33)") (class "Default")
      (node (ref "H1") (pin "33") (pinfunction "33_33") (pintype "passive"))
    )
    (net (code "76") (name "unconnected-(H1-Pad34)") (class "Default")
      (node (ref "H1") (pin "34") (pinfunction "34_34") (pintype "passive"))
    )
    (net (code "77") (name "unconnected-(H1-Pad35)") (class "Default")
      (node (ref "H1") (pin "35") (pinfunction "35_35") (pintype "passive"))
    )
    (net (code "78") (name "unconnected-(H1-Pad36)") (class "Default")
      (node (ref "H1") (pin "36") (pinfunction "36_36") (pintype "passive"))
    )
    (net (code "79") (name "unconnected-(H1-Pad37)") (class "Default")
      (node (ref "H1") (pin "37") (pinfunction "37_37") (pintype "passive"))
    )
    (net (code "80") (name "unconnected-(H1-Pad38)") (class "Default")
      (node (ref "H1") (pin "38") (pinfunction "38_38") (pintype "passive"))
    )
    (net (code "81") (name "unconnected-(H1-Pad39)") (class "Default")
      (node (ref "H1") (pin "39") (pinfunction "39_39") (pintype "passive"))
    )
    (net (code "82") (name "unconnected-(H1-Pad40)") (class "Default")
      (node (ref "H1") (pin "40") (pinfunction "40_40") (pintype "passive"))
    )
    (net (code "83") (name "unconnected-(H1-Pad42)") (class "Default")
      (node (ref "H1") (pin "42") (pinfunction "42_42") (pintype "passive"))
    )
    (net (code "84") (name "unconnected-(H1-Pad44)") (class "Default")
      (node (ref "H1") (pin "44") (pinfunction "44_44") (pintype "passive"))
    )
    (net (code "85") (name "unconnected-(H1-Pad45)") (class "Default")
      (node (ref "H1") (pin "45") (pinfunction "45_45") (pintype "passive"))
    )
    (net (code "86") (name "unconnected-(H1-Pad46)") (class "Default")
      (node (ref "H1") (pin "46") (pinfunction "46_46") (pintype "passive"))
    )
    (net (code "87") (name "unconnected-(H1-Pad47)") (class "Default")
      (node (ref "H1") (pin "47") (pinfunction "47_47") (pintype "passive"))
    )
    (net (code "88") (name "unconnected-(H1-Pad48)") (class "Default")
      (node (ref "H1") (pin "48") (pinfunction "48_48") (pintype "passive"))
    )
    (net (code "89") (name "unconnected-(H2-Pad1)") (class "Default")
      (node (ref "H2") (pin "1") (pinfunction "1_1") (pintype "passive"))
    )
    (net (code "90") (name "unconnected-(H2-Pad2)") (class "Default")
      (node (ref "H2") (pin "2") (pinfunction "2_2") (pintype "passive"))
    )
    (net (code "91") (name "unconnected-(H2-Pad3)") (class "Default")
      (node (ref "H2") (pin "3") (pinfunction "3_3") (pintype "passive"))
    )
    (net (code "92") (name "unconnected-(H2-Pad4)") (class "Default")
      (node (ref "H2") (pin "4") (pinfunction "4_4") (pintype "passive"))
    )
    (net (code "93") (name "unconnected-(H2-Pad5)") (class "Default")
      (node (ref "H2") (pin "5") (pinfunction "5_5") (pintype "passive"))
    )
    (net (code "94") (name "unconnected-(H2-Pad6)") (class "Default")
      (node (ref "H2") (pin "6") (pinfunction "6_6") (pintype "passive"))
    )
    (net (code "95") (name "unconnected-(H2-Pad7)") (class "Default")
      (node (ref "H2") (pin "7") (pinfunction "7_7") (pintype "passive"))
    )
    (net (code "96") (name "unconnected-(H2-Pad8)") (class "Default")
      (node (ref "H2") (pin "8") (pinfunction "8_8") (pintype "passive"))
    )
    (net (code "97") (name "unconnected-(H2-Pad9)") (class "Default")
      (node (ref "H2") (pin "9") (pinfunction "9_9") (pintype "passive"))
    )
    (net (code "98") (name "unconnected-(H2-Pad10)") (class "Default")
      (node (ref "H2") (pin "10") (pinfunction "10_10") (pintype "passive"))
    )
    (net (code "99") (name "unconnected-(H2-Pad11)") (class "Default")
      (node (ref "H2") (pin "11") (pinfunction "11_11") (pintype "passive"))
    )
    (net (code "100") (name "unconnected-(H2-Pad12)") (class "Default")
      (node (ref "H2") (pin "12") (pinfunction "12_12") (pintype "passive"))
    )
    (net (code "101") (name "unconnected-(H2-Pad13)") (class "Default")
      (node (ref "H2") (pin "13") (pinfunction "13_13") (pintype "passive"))
    )
    (net (code "102") (name "unconnected-(H2-Pad14)") (class "Default")
      (node (ref "H2") (pin "14") (pinfunction "14_14") (pintype "passive"))
    )
    (net (code "103") (name "unconnected-(H2-Pad15)") (class "Default")
      (node (ref "H2") (pin "15") (pinfunction "15_15") (pintype "passive"))
    )
    (net (code "104") (name "unconnected-(H2-Pad16)") (class "Default")
      (node (ref "H2") (pin "16") (pinfunction "16_16") (pintype "passive"))
    )
    (net (code "105") (name "unconnected-(H2-Pad17)") (class "Default")
      (node (ref "H2") (pin "17") (pinfunction "17_17") (pintype "passive"))
    )
    (net (code "106") (name "unconnected-(H2-Pad18)") (class "Default")
      (node (ref "H2") (pin "18") (pinfunction "18_18") (pintype "passive"))
    )
    (net (code "107") (name "unconnected-(H2-Pad19)") (class "Default")
      (node (ref "H2") (pin "19") (pinfunction "19_19") (pintype "passive"))
    )
    (net (code "108") (name "unconnected-(H2-Pad20)") (class "Default")
      (node (ref "H2") (pin "20") (pinfunction "20_20") (pintype "passive"))
    )
    (net (code "109") (name "unconnected-(H2-Pad21)") (class "Default")
      (node (ref "H2") (pin "21") (pinfunction "21_21") (pintype "passive"))
    )
    (net (code "110") (name "unconnected-(H2-Pad22)") (class "Default")
      (node (ref "H2") (pin "22") (pinfunction "22_22") (pintype "passive"))
    )
    (net (code "111") (name "unconnected-(H2-Pad23)") (class "Default")
      (node (ref "H2") (pin "23") (pinfunction "23_23") (pintype "passive"))
    )
    (net (code "112") (name "unconnected-(H2-Pad24)") (class "Default")
      (node (ref "H2") (pin "24") (pinfunction "24_24") (pintype "passive"))
    )
    (net (code "113") (name "unconnected-(H2-Pad31)") (class "Default")
      (node (ref "H2") (pin "31") (pinfunction "31_31") (pintype "passive"))
    )
    (net (code "114") (name "unconnected-(H2-Pad33)") (class "Default")
      (node (ref "H2") (pin "33") (pinfunction "33_33") (pintype "passive"))
    )
    (net (code "115") (name "unconnected-(H2-Pad35)") (class "Default")
      (node (ref "H2") (pin "35") (pinfunction "35_35") (pintype "passive"))
    )
    (net (code "116") (name "unconnected-(H2-Pad36)") (class "Default")
      (node (ref "H2") (pin "36") (pinfunction "36_36") (pintype "passive"))
    )
    (net (code "117") (name "unconnected-(H2-Pad37)") (class "Default")
      (node (ref "H2") (pin "37") (pinfunction "37_37") (pintype "passive"))
    )
    (net (code "118") (name "unconnected-(H2-Pad38)") (class "Default")
      (node (ref "H2") (pin "38") (pinfunction "38_38") (pintype "passive"))
    )
    (net (code "119") (name "unconnected-(H2-Pad39)") (class "Default")
      (node (ref "H2") (pin "39") (pinfunction "39_39") (pintype "passive"))
    )
    (net (code "120") (name "unconnected-(H2-Pad40)") (class "Default")
      (node (ref "H2") (pin "40") (pinfunction "40_40") (pintype "passive"))
    )
    (net (code "121") (name "unconnected-(H2-Pad41)") (class "Default")
      (node (ref "H2") (pin "41") (pinfunction "41_41") (pintype "passive"))
    )
    (net (code "122") (name "unconnected-(H2-Pad42)") (class "Default")
      (node (ref "H2") (pin "42") (pinfunction "42_42") (pintype "passive"))
    )
    (net (code "123") (name "unconnected-(H2-Pad43)") (class "Default")
      (node (ref "H2") (pin "43") (pinfunction "43_43") (pintype "passive"))
    )
    (net (code "124") (name "unconnected-(H2-Pad44)") (class "Default")
      (node (ref "H2") (pin "44") (pinfunction "44_44") (pintype "passive"))
    )
    (net (code "125") (name "unconnected-(H2-Pad47)") (class "Default")
      (node (ref "H2") (pin "47") (pinfunction "47_47") (pintype "passive"))
    )
    (net (code "126") (name "unconnected-(H2-Pad48)") (class "Default")
      (node (ref "H2") (pin "48") (pinfunction "48_48") (pintype "passive"))
    )
    (net (code "127") (name "unconnected-(H2-Pad49)") (class "Default")
      (node (ref "H2") (pin "49") (pinfunction "49_49") (pintype "passive"))
    )
    (net (code "128") (name "unconnected-(H2-Pad50)") (class "Default")
      (node (ref "H2") (pin "50") (pinfunction "50_50") (pintype "passive"))
    )
    (net (code "129") (name "unconnected-(H2-Pad51)") (class "Default")
      (node (ref "H2") (pin "51") (pinfunction "51_51") (pintype "passive"))
    )
    (net (code "130") (name "unconnected-(H2-Pad52)") (class "Default")
      (node (ref "H2") (pin "52") (pinfunction "52_52") (pintype "passive"))
    )
    (net (code "131") (name "unconnected-(H6-0{slash}RXD-Pad2)") (class "Default")
      (node (ref "H6") (pin "2") (pinfunction "0/RXD_2") (pintype "passive"))
    )
    (net (code "132") (name "unconnected-(H6-1{slash}TXD-Pad1)") (class "Default")
      (node (ref "H6") (pin "1") (pinfunction "1/TXD_1") (pintype "passive"))
    )
    (net (code "133") (name "unconnected-(H6-2{slash}INT0-Pad5)") (class "Default")
      (node (ref "H6") (pin "5") (pinfunction "2/INT0_5") (pintype "passive"))
    )
    (net (code "134") (name "unconnected-(H6-4-Pad7)") (class "Default")
      (node (ref "H6") (pin "7") (pinfunction "4_7") (pintype "passive"))
    )
    (net (code "135") (name "unconnected-(H6-7-Pad10)") (class "Default")
      (node (ref "H6") (pin "10") (pinfunction "7_10") (pintype "passive"))
    )
    (net (code "136") (name "unconnected-(H6-8-Pad11)") (class "Default")
      (node (ref "H6") (pin "11") (pinfunction "8_11") (pintype "passive"))
    )
    (net (code "137") (name "unconnected-(H6-12{slash}MISO-Pad22)") (class "Default")
      (node (ref "H6") (pin "22") (pinfunction "12/MISO_22") (pintype "passive"))
    )
    (net (code "138") (name "unconnected-(H6-13{slash}SCK-Pad21)") (class "Default")
      (node (ref "H6") (pin "21") (pinfunction "13/SCK_21") (pintype "passive"))
    )
    (net (code "139") (name "unconnected-(H6-RESET-Pad3)") (class "Default")
      (node (ref "H6") (pin "3") (pinfunction "RESET_3") (pintype "passive"))
    )
    (net (code "140") (name "unconnected-(H6-RESET-Pad15)") (class "Default")
      (node (ref "H6") (pin "15") (pinfunction "RESET_15") (pintype "passive"))
    )
    (net (code "141") (name "unconnected-(H6-~3{slash}INT1-Pad6)") (class "Default")
      (node (ref "H6") (pin "6") (pinfunction "~3/INT1_6") (pintype "passive"))
    )
    (net (code "142") (name "unconnected-(H6-~5-Pad8)") (class "Default")
      (node (ref "H6") (pin "8") (pinfunction "~5_8") (pintype "passive"))
    )
    (net (code "143") (name "unconnected-(H6-~6-Pad9)") (class "Default")
      (node (ref "H6") (pin "9") (pinfunction "~6_9") (pintype "passive"))
    )
    (net (code "144") (name "unconnected-(H6-~9-Pad12)") (class "Default")
      (node (ref "H6") (pin "12") (pinfunction "~9_12") (pintype "passive"))
    )
  )
)
